# motor6.net
KiCad netlist of a schematic drawn in EAGLE
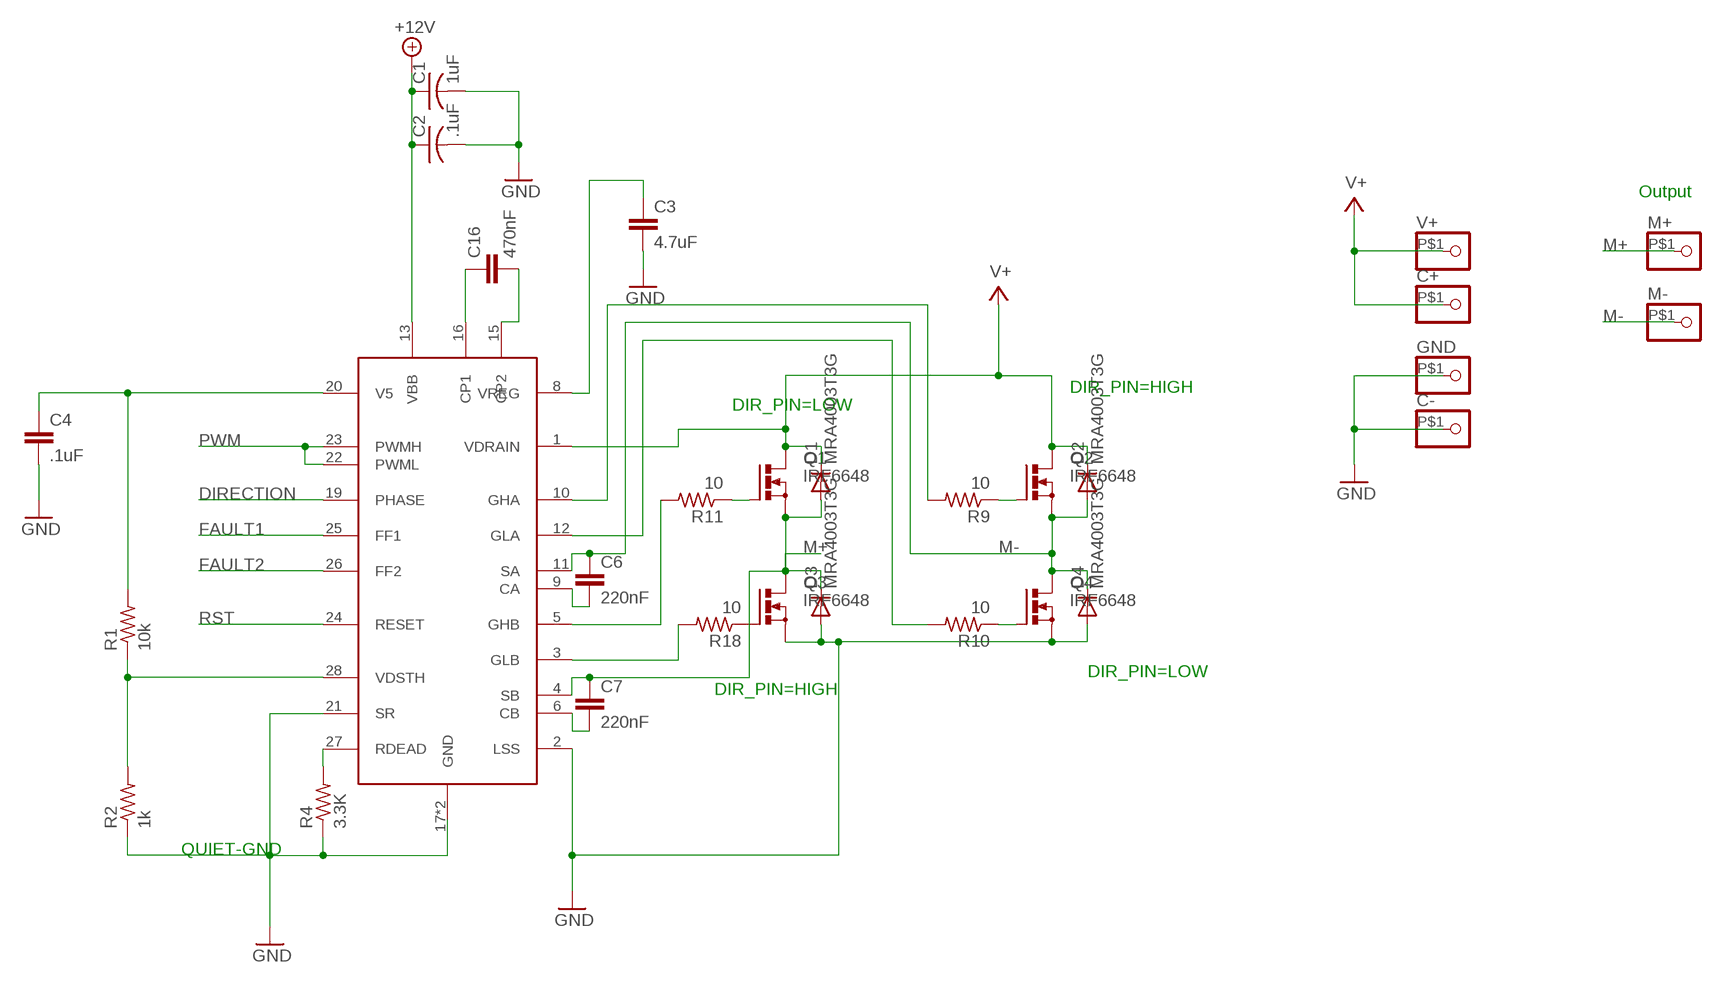
[diagram p0: schematic, sheet 1]
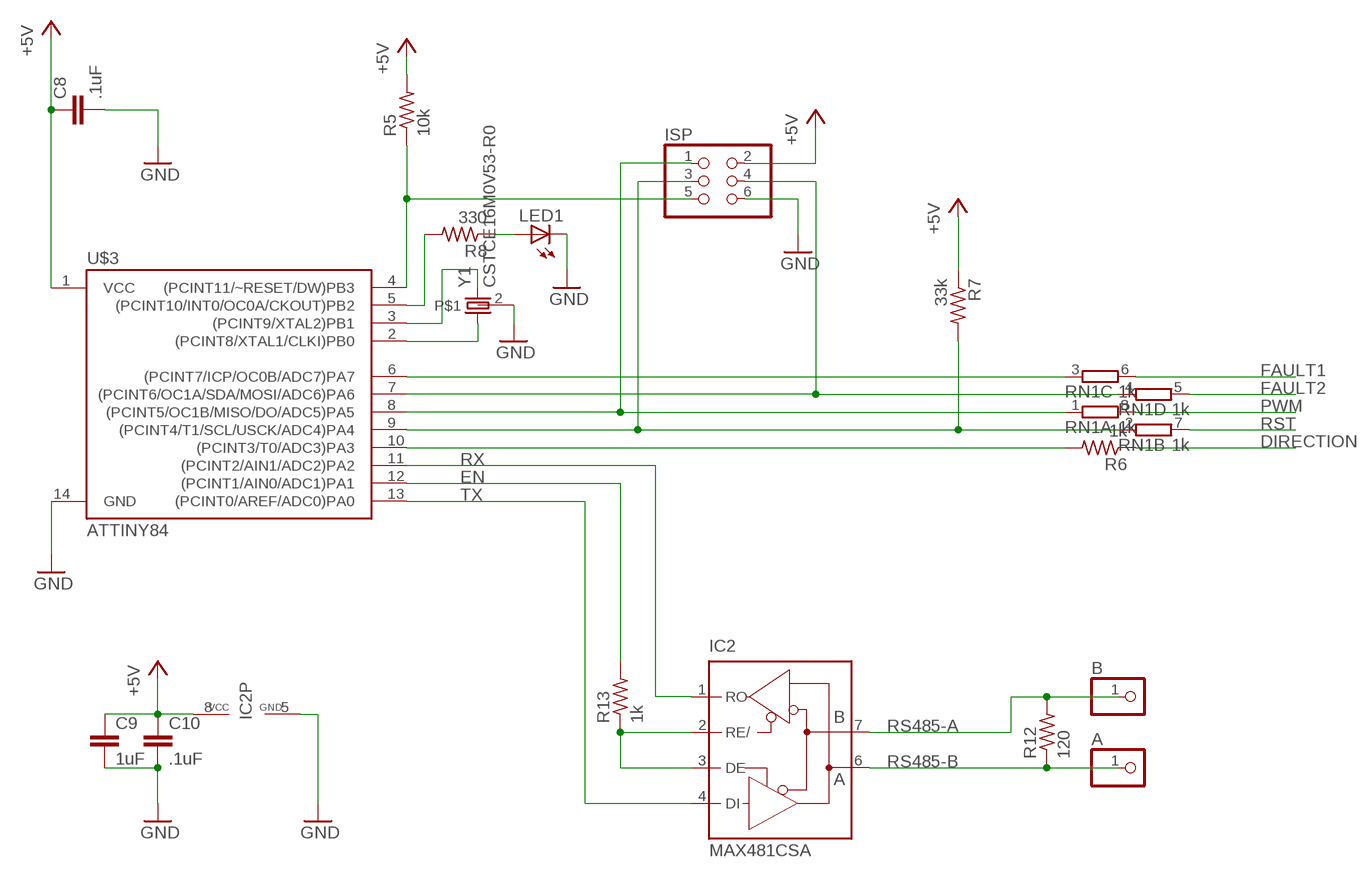
[diagram p1: schematic, sheet 2]
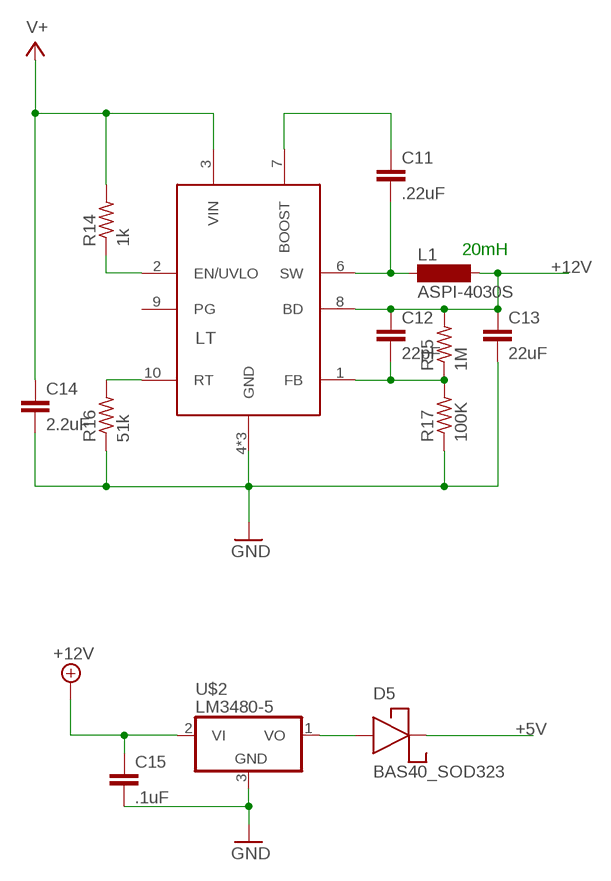
[diagram p2: schematic, sheet 3]

(export (version "E")
  (design (tool "Eeschema 10.0.6"))
  (components
    (comp (ref "C11")
      (value ".22uF")
      (footprint "eagle-import:C0603")
      (libsource (lib "eagle-import") (part "C-EUC0603"))
    )
    (comp (ref "C12")
      (value "22pF")
      (footprint "eagle-import:C0603")
      (libsource (lib "eagle-import") (part "C-EUC0603"))
    )
    (comp (ref "C13")
      (value "22uF")
      (footprint "eagle-import:C0805")
      (libsource (lib "eagle-import") (part "C-EUC0805"))
    )
    (comp (ref "C14")
      (value "2.2uF")
      (footprint "eagle-import:C0603")
      (libsource (lib "eagle-import") (part "C-EUC0603"))
    )
    (comp (ref "C15")
      (value ".1uF")
      (footprint "eagle-import:C0603")
      (libsource (lib "eagle-import") (part "C-EUC0603"))
    )
    (comp (ref "D5")
      (value "BAS40_SOD323")
      (footprint "eagle-import:SOD323")
      (libsource (lib "eagle-import") (part "BAS40_SOD323"))
    )
    (comp (ref "L1")
      (value "ASPI-4030S")
      (footprint "eagle-import:ASPI-4030S")
      (libsource (lib "eagle-import") (part "ASPI-4030S"))
    )
    (comp (ref "LT")
      (value "LT3990")
      (footprint "eagle-import:DFN10-3X3")
      (libsource (lib "eagle-import") (part "LT3990"))
    )
    (comp (ref "R14")
      (value "1k")
      (footprint "eagle-import:R0603")
      (libsource (lib "eagle-import") (part "R-US_R0603"))
    )
    (comp (ref "R15")
      (value "1M")
      (footprint "eagle-import:R0603")
      (libsource (lib "eagle-import") (part "R-US_R0603"))
    )
    (comp (ref "R16")
      (value "51k")
      (footprint "eagle-import:R0603")
      (libsource (lib "eagle-import") (part "R-US_R0603"))
    )
    (comp (ref "R17")
      (value "100K")
      (footprint "eagle-import:R0603")
      (libsource (lib "eagle-import") (part "R-US_R0603"))
    )
    (comp (ref "U$2")
      (value "LM3480-5")
      (footprint "eagle-import:SOT23")
      (libsource (lib "eagle-import") (part "LM3480-5"))
    )
    (comp (ref "ALLGR")
      (value "ALLEGRO-A3921")
      (footprint "eagle-import:TSSOP28")
      (libsource (lib "eagle-import") (part "ALLEGRO-A3921"))
    )
    (comp (ref "C+")
      (value "PINHD-1X1")
      (footprint "eagle-import:1X01")
      (libsource (lib "eagle-import") (part "PINHD-1X1"))
    )
    (comp (ref "C-")
      (value "PINHD-1X1")
      (footprint "eagle-import:1X01")
      (libsource (lib "eagle-import") (part "PINHD-1X1"))
    )
    (comp (ref "C1")
      (value "1uF")
      (footprint "eagle-import:C0603")
      (libsource (lib "eagle-import") (part "C-USC0603"))
    )
    (comp (ref "C2")
      (value ".1uF")
      (footprint "eagle-import:C0603")
      (libsource (lib "eagle-import") (part "C-USC0603"))
    )
    (comp (ref "C3")
      (value "4.7uF")
      (footprint "eagle-import:C0603")
      (libsource (lib "eagle-import") (part "C-EUC0603"))
    )
    (comp (ref "C4")
      (value ".1uF")
      (footprint "eagle-import:C0603")
      (libsource (lib "eagle-import") (part "C-EUC0603"))
    )
    (comp (ref "C6")
      (value "220nF")
      (footprint "eagle-import:C0603")
      (libsource (lib "eagle-import") (part "C-EUC0603"))
    )
    (comp (ref "C7")
      (value "220nF")
      (footprint "eagle-import:C0603")
      (libsource (lib "eagle-import") (part "C-EUC0603"))
    )
    (comp (ref "C16")
      (value "470nF")
      (footprint "eagle-import:C0603")
      (libsource (lib "eagle-import") (part "C-EUC0603"))
    )
    (comp (ref "D1")
      (value "MRA4003T3G")
      (footprint "eagle-import:SMA")
      (libsource (lib "eagle-import") (part "MRA4003T3G"))
    )
    (comp (ref "D2")
      (value "MRA4003T3G")
      (footprint "eagle-import:SMA")
      (libsource (lib "eagle-import") (part "MRA4003T3G"))
    )
    (comp (ref "D3")
      (value "MRA4003T3G")
      (footprint "eagle-import:SMA")
      (libsource (lib "eagle-import") (part "MRA4003T3G"))
    )
    (comp (ref "D4")
      (value "MRA4003T3G")
      (footprint "eagle-import:SMA")
      (libsource (lib "eagle-import") (part "MRA4003T3G"))
    )
    (comp (ref "GND")
      (value "PINHD-1X1")
      (footprint "eagle-import:1X01")
      (libsource (lib "eagle-import") (part "PINHD-1X1"))
    )
    (comp (ref "M+")
      (value "PINHD-1X1")
      (footprint "eagle-import:1X01")
      (libsource (lib "eagle-import") (part "PINHD-1X1"))
    )
    (comp (ref "M-")
      (value "PINHD-1X1")
      (footprint "eagle-import:1X01")
      (libsource (lib "eagle-import") (part "PINHD-1X1"))
    )
    (comp (ref "Q1")
      (value "IRF6648")
      (footprint "eagle-import:DIRECTFET-MOD")
      (libsource (lib "eagle-import") (part "IRF6648"))
    )
    (comp (ref "Q2")
      (value "IRF6648")
      (footprint "eagle-import:DIRECTFET-MOD")
      (libsource (lib "eagle-import") (part "IRF6648"))
    )
    (comp (ref "Q3")
      (value "IRF6648")
      (footprint "eagle-import:DIRECTFET")
      (libsource (lib "eagle-import") (part "transistor-power_IRF6648"))
    )
    (comp (ref "Q4")
      (value "IRF6648")
      (footprint "eagle-import:DIRECTFET")
      (libsource (lib "eagle-import") (part "transistor-power_IRF6648"))
    )
    (comp (ref "R1")
      (value "10k")
      (footprint "eagle-import:R0603")
      (libsource (lib "eagle-import") (part "R-US_R0603"))
    )
    (comp (ref "R2")
      (value "1k")
      (footprint "eagle-import:R0603")
      (libsource (lib "eagle-import") (part "R-US_R0603"))
    )
    (comp (ref "R4")
      (value "3.3K")
      (footprint "eagle-import:R0603")
      (libsource (lib "eagle-import") (part "R-US_R0603"))
    )
    (comp (ref "R9")
      (value "10")
      (footprint "eagle-import:R0603")
      (libsource (lib "eagle-import") (part "R-US_R0603"))
    )
    (comp (ref "R10")
      (value "10")
      (footprint "eagle-import:R0603")
      (libsource (lib "eagle-import") (part "R-US_R0603"))
    )
    (comp (ref "R11")
      (value "10")
      (footprint "eagle-import:R0603")
      (libsource (lib "eagle-import") (part "R-US_R0603"))
    )
    (comp (ref "R18")
      (value "10")
      (footprint "eagle-import:R0603")
      (libsource (lib "eagle-import") (part "R-US_R0603"))
    )
    (comp (ref "V+")
      (value "PINHD-1X1")
      (footprint "eagle-import:1X01")
      (libsource (lib "eagle-import") (part "PINHD-1X1"))
    )
    (comp (ref "A")
      (value "PINHD-1X1")
      (footprint "eagle-import:1X01")
      (libsource (lib "eagle-import") (part "pinhead_PINHD-1X1"))
    )
    (comp (ref "B")
      (value "PINHD-1X1")
      (footprint "eagle-import:1X01")
      (libsource (lib "eagle-import") (part "pinhead_PINHD-1X1"))
    )
    (comp (ref "C8")
      (value ".1uF")
      (footprint "eagle-import:C0603")
      (libsource (lib "eagle-import") (part "C-EUC0603"))
    )
    (comp (ref "C9")
      (value "1uF")
      (footprint "eagle-import:C0603")
      (libsource (lib "eagle-import") (part "C-EUC0603"))
    )
    (comp (ref "C10")
      (value ".1uF")
      (footprint "eagle-import:C0603")
      (libsource (lib "eagle-import") (part "C-EUC0603"))
    )
    (comp (ref "IC2")
      (value "MAX481CSA")
      (footprint "eagle-import:SO08")
      (fields (field (name "MF") "MAXIM"))
      (libsource (lib "eagle-import") (part "MAX481CSA"))
    )
    (comp (ref "ISP")
      (value "PINHD-2X3")
      (footprint "eagle-import:2X03")
      (libsource (lib "eagle-import") (part "PINHD-2X3"))
    )
    (comp (ref "LED1")
      (value "LEDCHIPLED_0603")
      (footprint "eagle-import:CHIPLED_0603")
      (libsource (lib "eagle-import") (part "LEDCHIPLED_0603"))
    )
    (comp (ref "R5")
      (value "10k")
      (footprint "eagle-import:R0603")
      (libsource (lib "eagle-import") (part "R-US_R0603"))
    )
    (comp (ref "R6")
      (value "1k")
      (footprint "eagle-import:R0603")
      (libsource (lib "eagle-import") (part "R-US_R0603"))
    )
    (comp (ref "R7")
      (value "33k")
      (footprint "eagle-import:R0603")
      (libsource (lib "eagle-import") (part "R-US_R0603"))
    )
    (comp (ref "R8")
      (value "330")
      (footprint "eagle-import:R0603")
      (libsource (lib "eagle-import") (part "R-US_R0603"))
    )
    (comp (ref "R12")
      (value "120")
      (footprint "eagle-import:R0603")
      (libsource (lib "eagle-import") (part "R-US_R0603"))
    )
    (comp (ref "R13")
      (value "1k")
      (footprint "eagle-import:R0603")
      (libsource (lib "eagle-import") (part "R-US_R0603"))
    )
    (comp (ref "RN1")
      (value "1k")
      (footprint "eagle-import:EXB38V")
      (libsource (lib "eagle-import") (part "4R-NEXB38V"))
    )
    (comp (ref "U$3")
      (value "ATTINY84")
      (footprint "eagle-import:SO14")
      (libsource (lib "eagle-import") (part "ATTINY84"))
    )
    (comp (ref "Y1")
      (value "CSTCE16M0V53-R0")
      (footprint "eagle-import:MYSMD2_RESONATOR")
      (libsource (lib "eagle-import") (part "CSTCE16M0V53-R0"))
    )
  )
  (nets
    (net (code "1") (name "+5V") (class "Default")
      (node (ref "C10") (pin "1") (pinfunction "1_1") (pintype "passive"))
      (node (ref "C8") (pin "1") (pinfunction "1_1") (pintype "passive"))
      (node (ref "C9") (pin "1") (pinfunction "1_1") (pintype "passive"))
      (node (ref "D5") (pin "1") (pinfunction "P$2_1") (pintype "bidirectional"))
      (node (ref "IC2") (pin "8") (pinfunction "VCC_8") (pintype "power_in"))
      (node (ref "ISP") (pin "2") (pinfunction "2_2") (pintype "passive"))
      (node (ref "R5") (pin "2") (pinfunction "2_2") (pintype "passive"))
      (node (ref "R7") (pin "1") (pinfunction "1_1") (pintype "passive"))
      (node (ref "U$3") (pin "1") (pinfunction "VCC_1") (pintype "bidirectional"))
    )
    (net (code "2") (name "+12V") (class "Default")
      (node (ref "ALLGR") (pin "13") (pinfunction "VBB_13") (pintype "bidirectional"))
      (node (ref "C1") (pin "1") (pinfunction "1_1") (pintype "passive"))
      (node (ref "C12") (pin "1") (pinfunction "1_1") (pintype "passive"))
      (node (ref "C13") (pin "1") (pinfunction "1_1") (pintype "passive"))
      (node (ref "C15") (pin "1") (pinfunction "1_1") (pintype "passive"))
      (node (ref "C2") (pin "1") (pinfunction "1_1") (pintype "passive"))
      (node (ref "L1") (pin "P$2") (pinfunction "2_P$2") (pintype "passive"))
      (node (ref "LT") (pin "8") (pinfunction "BD_8") (pintype "bidirectional"))
      (node (ref "R15") (pin "2") (pinfunction "2_2") (pintype "passive"))
      (node (ref "U$2") (pin "2") (pinfunction "VI_2") (pintype "input"))
    )
    (net (code "3") (name "DIRECTION") (class "Default")
      (node (ref "ALLGR") (pin "19") (pinfunction "PHASE_19") (pintype "bidirectional"))
      (node (ref "R6") (pin "1") (pinfunction "1_1") (pintype "passive"))
    )
    (net (code "4") (name "EN") (class "Default")
      (node (ref "R13") (pin "2") (pinfunction "2_2") (pintype "passive"))
      (node (ref "U$3") (pin "12") (pinfunction "(PCINT1/AIN0/ADC1)PA1_12") (pintype "bidirectional"))
    )
    (net (code "5") (name "FAULT1") (class "Default")
      (node (ref "ALLGR") (pin "25") (pinfunction "FF1_25") (pintype "bidirectional"))
      (node (ref "RN1") (pin "6") (pinfunction "2_6") (pintype "passive"))
    )
    (net (code "6") (name "FAULT2") (class "Default")
      (node (ref "ALLGR") (pin "26") (pinfunction "FF2_26") (pintype "bidirectional"))
      (node (ref "RN1") (pin "5") (pinfunction "2_5") (pintype "passive"))
    )
    (net (code "7") (name "GND") (class "Default")
      (node (ref "ALLGR") (pin "17") (pinfunction "GND_17") (pintype "bidirectional"))
      (node (ref "ALLGR") (pin "2") (pinfunction "LSS_2") (pintype "bidirectional"))
      (node (ref "ALLGR") (pin "21") (pinfunction "SR_21") (pintype "bidirectional"))
      (node (ref "ALLGR") (pin "P$1") (pinfunction "GND_P$1") (pintype "bidirectional"))
      (node (ref "C-") (pin "P$1") (pinfunction "1_P$1") (pintype "passive"))
      (node (ref "C1") (pin "2") (pinfunction "2_2") (pintype "passive"))
      (node (ref "C10") (pin "2") (pinfunction "2_2") (pintype "passive"))
      (node (ref "C13") (pin "2") (pinfunction "2_2") (pintype "passive"))
      (node (ref "C14") (pin "2") (pinfunction "2_2") (pintype "passive"))
      (node (ref "C15") (pin "2") (pinfunction "2_2") (pintype "passive"))
      (node (ref "C2") (pin "2") (pinfunction "2_2") (pintype "passive"))
      (node (ref "C3") (pin "2") (pinfunction "2_2") (pintype "passive"))
      (node (ref "C4") (pin "2") (pinfunction "2_2") (pintype "passive"))
      (node (ref "C8") (pin "2") (pinfunction "2_2") (pintype "passive"))
      (node (ref "C9") (pin "2") (pinfunction "2_2") (pintype "passive"))
      (node (ref "D3") (pin "A") (pinfunction "A_A") (pintype "passive"))
      (node (ref "D4") (pin "A") (pinfunction "A_A") (pintype "passive"))
      (node (ref "GND") (pin "P$1") (pinfunction "1_P$1") (pintype "passive"))
      (node (ref "IC2") (pin "5") (pinfunction "GND_5") (pintype "power_in"))
      (node (ref "ISP") (pin "6") (pinfunction "6_6") (pintype "passive"))
      (node (ref "LED1") (pin "C") (pinfunction "C_C") (pintype "passive"))
      (node (ref "LT") (pin "4") (pinfunction "GND_4") (pintype "bidirectional"))
      (node (ref "LT") (pin "5") (pinfunction "GND_5") (pintype "bidirectional"))
      (node (ref "LT") (pin "EXP") (pinfunction "GND_EXP") (pintype "bidirectional"))
      (node (ref "Q3") (pin "S@1") (pinfunction "S_S@1") (pintype "passive"))
      (node (ref "Q3") (pin "S@2") (pinfunction "S_S@2") (pintype "passive"))
      (node (ref "Q4") (pin "S@1") (pinfunction "S_S@1") (pintype "passive"))
      (node (ref "Q4") (pin "S@2") (pinfunction "S_S@2") (pintype "passive"))
      (node (ref "R16") (pin "1") (pinfunction "1_1") (pintype "passive"))
      (node (ref "R17") (pin "1") (pinfunction "1_1") (pintype "passive"))
      (node (ref "R2") (pin "1") (pinfunction "1_1") (pintype "passive"))
      (node (ref "R4") (pin "1") (pinfunction "1_1") (pintype "passive"))
      (node (ref "U$2") (pin "3") (pinfunction "GND_3") (pintype "input"))
      (node (ref "U$3") (pin "14") (pinfunction "GND_14") (pintype "bidirectional"))
      (node (ref "Y1") (pin "2") (pinfunction "P$1_2") (pintype "bidirectional"))
    )
    (net (code "8") (name "M+") (class "Default")
      (node (ref "ALLGR") (pin "4") (pinfunction "SB_4") (pintype "bidirectional"))
      (node (ref "C7") (pin "1") (pinfunction "1_1") (pintype "passive"))
      (node (ref "D1") (pin "A") (pinfunction "A_A") (pintype "passive"))
      (node (ref "D3") (pin "C") (pinfunction "C_C") (pintype "passive"))
      (node (ref "M+") (pin "P$1") (pinfunction "1_P$1") (pintype "passive"))
      (node (ref "Q1") (pin "S@1") (pinfunction "S_S@1") (pintype "passive"))
      (node (ref "Q1") (pin "S@2") (pinfunction "S_S@2") (pintype "passive"))
      (node (ref "Q3") (pin "D@1") (pinfunction "D_D@1") (pintype "passive"))
      (node (ref "Q3") (pin "D@2") (pinfunction "D_D@2") (pintype "passive"))
      (node (ref "Q3") (pin "D@3") (pinfunction "D_D@3") (pintype "passive"))
      (node (ref "Q3") (pin "D@4") (pinfunction "D_D@4") (pintype "passive"))
    )
    (net (code "9") (name "M-") (class "Default")
      (node (ref "ALLGR") (pin "11") (pinfunction "SA_11") (pintype "bidirectional"))
      (node (ref "C6") (pin "1") (pinfunction "1_1") (pintype "passive"))
      (node (ref "D2") (pin "A") (pinfunction "A_A") (pintype "passive"))
      (node (ref "D4") (pin "C") (pinfunction "C_C") (pintype "passive"))
      (node (ref "M-") (pin "P$1") (pinfunction "1_P$1") (pintype "passive"))
      (node (ref "Q2") (pin "S@1") (pinfunction "S_S@1") (pintype "passive"))
      (node (ref "Q2") (pin "S@2") (pinfunction "S_S@2") (pintype "passive"))
      (node (ref "Q4") (pin "D@1") (pinfunction "D_D@1") (pintype "passive"))
      (node (ref "Q4") (pin "D@2") (pinfunction "D_D@2") (pintype "passive"))
      (node (ref "Q4") (pin "D@3") (pinfunction "D_D@3") (pintype "passive"))
      (node (ref "Q4") (pin "D@4") (pinfunction "D_D@4") (pintype "passive"))
    )
    (net (code "10") (name "Net-(ALLGR-CA)") (class "Default")
      (node (ref "ALLGR") (pin "9") (pinfunction "CA_9") (pintype "bidirectional"))
      (node (ref "C6") (pin "2") (pinfunction "2_2") (pintype "passive"))
    )
    (net (code "11") (name "Net-(ALLGR-CB)") (class "Default")
      (node (ref "ALLGR") (pin "6") (pinfunction "CB_6") (pintype "bidirectional"))
      (node (ref "C7") (pin "2") (pinfunction "2_2") (pintype "passive"))
    )
    (net (code "12") (name "Net-(ALLGR-CP1)") (class "Default")
      (node (ref "ALLGR") (pin "16") (pinfunction "CP1_16") (pintype "bidirectional"))
      (node (ref "C16") (pin "1") (pinfunction "1_1") (pintype "passive"))
    )
    (net (code "13") (name "Net-(ALLGR-CP2)") (class "Default")
      (node (ref "ALLGR") (pin "15") (pinfunction "CP2_15") (pintype "bidirectional"))
      (node (ref "C16") (pin "2") (pinfunction "2_2") (pintype "passive"))
    )
    (net (code "14") (name "Net-(ALLGR-GHA)") (class "Default")
      (node (ref "ALLGR") (pin "10") (pinfunction "GHA_10") (pintype "bidirectional"))
      (node (ref "R9") (pin "2") (pinfunction "2_2") (pintype "passive"))
    )
    (net (code "15") (name "Net-(ALLGR-GHB)") (class "Default")
      (node (ref "ALLGR") (pin "5") (pinfunction "GHB_5") (pintype "bidirectional"))
      (node (ref "R11") (pin "2") (pinfunction "2_2") (pintype "passive"))
    )
    (net (code "16") (name "Net-(ALLGR-GLA)") (class "Default")
      (node (ref "ALLGR") (pin "12") (pinfunction "GLA_12") (pintype "bidirectional"))
      (node (ref "R10") (pin "2") (pinfunction "2_2") (pintype "passive"))
    )
    (net (code "17") (name "Net-(ALLGR-GLB)") (class "Default")
      (node (ref "ALLGR") (pin "3") (pinfunction "GLB_3") (pintype "bidirectional"))
      (node (ref "R18") (pin "2") (pinfunction "2_2") (pintype "passive"))
    )
    (net (code "18") (name "Net-(ALLGR-RDEAD)") (class "Default")
      (node (ref "ALLGR") (pin "27") (pinfunction "RDEAD_27") (pintype "bidirectional"))
      (node (ref "R4") (pin "2") (pinfunction "2_2") (pintype "passive"))
    )
    (net (code "19") (name "Net-(ALLGR-V5)") (class "Default")
      (node (ref "ALLGR") (pin "20") (pinfunction "V5_20") (pintype "bidirectional"))
      (node (ref "C4") (pin "1") (pinfunction "1_1") (pintype "passive"))
      (node (ref "R1") (pin "2") (pinfunction "2_2") (pintype "passive"))
    )
    (net (code "20") (name "Net-(ALLGR-VDSTH)") (class "Default")
      (node (ref "ALLGR") (pin "28") (pinfunction "VDSTH_28") (pintype "bidirectional"))
      (node (ref "R1") (pin "1") (pinfunction "1_1") (pintype "passive"))
      (node (ref "R2") (pin "2") (pinfunction "2_2") (pintype "passive"))
    )
    (net (code "21") (name "Net-(ALLGR-VREG)") (class "Default")
      (node (ref "ALLGR") (pin "8") (pinfunction "VREG_8") (pintype "bidirectional"))
      (node (ref "C3") (pin "1") (pinfunction "1_1") (pintype "passive"))
    )
    (net (code "22") (name "Net-(D5-P$1)") (class "Default")
      (node (ref "D5") (pin "2") (pinfunction "P$1_2") (pintype "bidirectional"))
      (node (ref "U$2") (pin "1") (pinfunction "VO_1") (pintype "passive"))
    )
    (net (code "23") (name "Net-(IC2A-DE)") (class "Default")
      (node (ref "IC2") (pin "2") (pinfunction "RE/_2") (pintype "input"))
      (node (ref "IC2") (pin "3") (pinfunction "DE_3") (pintype "input"))
      (node (ref "R13") (pin "1") (pinfunction "1_1") (pintype "passive"))
    )
    (net (code "24") (name "Net-(L1-1)") (class "Default")
      (node (ref "C11") (pin "2") (pinfunction "2_2") (pintype "passive"))
      (node (ref "L1") (pin "P$1") (pinfunction "1_P$1") (pintype "passive"))
      (node (ref "LT") (pin "6") (pinfunction "SW_6") (pintype "bidirectional"))
    )
    (net (code "25") (name "Net-(LED1-PadA)") (class "Default")
      (node (ref "LED1") (pin "A") (pinfunction "A_A") (pintype "passive"))
      (node (ref "R8") (pin "1") (pinfunction "1_1") (pintype "passive"))
    )
    (net (code "26") (name "Net-(LT-BOOST)") (class "Default")
      (node (ref "C11") (pin "1") (pinfunction "1_1") (pintype "passive"))
      (node (ref "LT") (pin "7") (pinfunction "BOOST_7") (pintype "bidirectional"))
    )
    (net (code "27") (name "Net-(LT-EN{slash}UVLO)") (class "Default")
      (node (ref "LT") (pin "2") (pinfunction "EN/UVLO_2") (pintype "bidirectional"))
      (node (ref "R14") (pin "1") (pinfunction "1_1") (pintype "passive"))
    )
    (net (code "28") (name "Net-(LT-FB)") (class "Default")
      (node (ref "C12") (pin "2") (pinfunction "2_2") (pintype "passive"))
      (node (ref "LT") (pin "1") (pinfunction "FB_1") (pintype "bidirectional"))
      (node (ref "R15") (pin "1") (pinfunction "1_1") (pintype "passive"))
      (node (ref "R17") (pin "2") (pinfunction "2_2") (pintype "passive"))
    )
    (net (code "29") (name "Net-(LT-RT)") (class "Default")
      (node (ref "LT") (pin "10") (pinfunction "RT_10") (pintype "bidirectional"))
      (node (ref "R16") (pin "2") (pinfunction "2_2") (pintype "passive"))
    )
    (net (code "30") (name "Net-(Q1-PadG)") (class "Default")
      (node (ref "Q1") (pin "G") (pinfunction "G_G") (pintype "passive"))
      (node (ref "R11") (pin "1") (pinfunction "1_1") (pintype "passive"))
    )
    (net (code "31") (name "Net-(Q2-PadG)") (class "Default")
      (node (ref "Q2") (pin "G") (pinfunction "G_G") (pintype "passive"))
      (node (ref "R9") (pin "1") (pinfunction "1_1") (pintype "passive"))
    )
    (net (code "32") (name "Net-(Q3-PadG)") (class "Default")
      (node (ref "Q3") (pin "G") (pinfunction "G_G") (pintype "passive"))
      (node (ref "R18") (pin "1") (pinfunction "1_1") (pintype "passive"))
    )
    (net (code "33") (name "Net-(Q4-PadG)") (class "Default")
      (node (ref "Q4") (pin "G") (pinfunction "G_G") (pintype "passive"))
      (node (ref "R10") (pin "1") (pinfunction "1_1") (pintype "passive"))
    )
    (net (code "34") (name "Net-(RN1B-1)") (class "Default")
      (node (ref "ISP") (pin "3") (pinfunction "3_3") (pintype "passive"))
      (node (ref "R7") (pin "2") (pinfunction "2_2") (pintype "passive"))
      (node (ref "RN1") (pin "2") (pinfunction "1_2") (pintype "passive"))
      (node (ref "U$3") (pin "9") (pinfunction "(PCINT4/T1/SCL/USCK/ADC4)PA4_9") (pintype "bidirectional"))
    )
    (net (code "35") (name "Net-(RN1C-1)") (class "Default")
      (node (ref "RN1") (pin "3") (pinfunction "1_3") (pintype "passive"))
      (node (ref "U$3") (pin "6") (pinfunction "(PCINT7/ICP/OC0B/ADC7)PA7_6") (pintype "bidirectional"))
    )
    (net (code "36") (name "Net-(RN1D-1)") (class "Default")
      (node (ref "ISP") (pin "4") (pinfunction "4_4") (pintype "passive"))
      (node (ref "RN1") (pin "4") (pinfunction "1_4") (pintype "passive"))
      (node (ref "U$3") (pin "7") (pinfunction "(PCINT6/OC1A/SDA/MOSI/ADC6)PA6_7") (pintype "bidirectional"))
    )
    (net (code "37") (name "Net-(U$3-(PCINT3{slash}T0{slash}ADC3)PA3)") (class "Default")
      (node (ref "R6") (pin "2") (pinfunction "2_2") (pintype "passive"))
      (node (ref "U$3") (pin "10") (pinfunction "(PCINT3/T0/ADC3)PA3_10") (pintype "bidirectional"))
    )
    (net (code "38") (name "Net-(U$3-(PCINT5{slash}OC1B{slash}MISO{slash}DO{slash}ADC5)PA5)") (class "Default")
      (node (ref "ISP") (pin "1") (pinfunction "1_1") (pintype "passive"))
      (node (ref "RN1") (pin "1") (pinfunction "1_1") (pintype "passive"))
      (node (ref "U$3") (pin "8") (pinfunction "(PCINT5/OC1B/MISO/DO/ADC5)PA5_8") (pintype "bidirectional"))
    )
    (net (code "39") (name "Net-(U$3-(PCINT8{slash}XTAL1{slash}CLKI)PB0)") (class "Default")
      (node (ref "U$3") (pin "2") (pinfunction "(PCINT8/XTAL1/CLKI)PB0_2") (pintype "bidirectional"))
      (node (ref "Y1") (pin "1") (pinfunction "1_1") (pintype "passive"))
    )
    (net (code "40") (name "Net-(U$3-(PCINT9{slash}XTAL2)PB1)") (class "Default")
      (node (ref "U$3") (pin "3") (pinfunction "(PCINT9/XTAL2)PB1_3") (pintype "bidirectional"))
      (node (ref "Y1") (pin "3") (pinfunction "2_3") (pintype "passive"))
    )
    (net (code "41") (name "Net-(U$3-(PCINT10{slash}INT0{slash}OC0A{slash}CKOUT)PB2)") (class "Default")
      (node (ref "R8") (pin "2") (pinfunction "2_2") (pintype "passive"))
      (node (ref "U$3") (pin "5") (pinfunction "(PCINT10/INT0/OC0A/CKOUT)PB2_5") (pintype "bidirectional"))
    )
    (net (code "42") (name "Net-(U$3-(PCINT11{slash}~{RESET{slash}DW})PB3)") (class "Default")
      (node (ref "ISP") (pin "5") (pinfunction "5_5") (pintype "passive"))
      (node (ref "R5") (pin "1") (pinfunction "1_1") (pintype "passive"))
      (node (ref "U$3") (pin "4") (pinfunction "(PCINT11/~{RESET/DW})PB3_4") (pintype "bidirectional"))
    )
    (net (code "43") (name "PWM") (class "Default")
      (node (ref "ALLGR") (pin "22") (pinfunction "PWML_22") (pintype "bidirectional"))
      (node (ref "ALLGR") (pin "23") (pinfunction "PWMH_23") (pintype "bidirectional"))
      (node (ref "RN1") (pin "8") (pinfunction "2_8") (pintype "passive"))
    )
    (net (code "44") (name "RS485-A") (class "Default")
      (node (ref "B") (pin "1") (pinfunction "1_1") (pintype "passive"))
      (node (ref "IC2") (pin "7") (pinfunction "B_7") (pintype "passive"))
      (node (ref "R12") (pin "2") (pinfunction "2_2") (pintype "passive"))
    )
    (net (code "45") (name "RS485-B") (class "Default")
      (node (ref "A") (pin "1") (pinfunction "1_1") (pintype "passive"))
      (node (ref "IC2") (pin "6") (pinfunction "A_6") (pintype "passive"))
      (node (ref "R12") (pin "1") (pinfunction "1_1") (pintype "passive"))
    )
    (net (code "46") (name "RST") (class "Default")
      (node (ref "ALLGR") (pin "24") (pinfunction "RESET_24") (pintype "bidirectional"))
      (node (ref "RN1") (pin "7") (pinfunction "2_7") (pintype "passive"))
    )
    (net (code "47") (name "RX") (class "Default")
      (node (ref "IC2") (pin "1") (pinfunction "RO_1") (pintype "output"))
      (node (ref "U$3") (pin "11") (pinfunction "(PCINT2/AIN1/ADC2)PA2_11") (pintype "bidirectional"))
    )
    (net (code "48") (name "TX") (class "Default")
      (node (ref "IC2") (pin "4") (pinfunction "DI_4") (pintype "input"))
      (node (ref "U$3") (pin "13") (pinfunction "(PCINT0/AREF/ADC0)PA0_13") (pintype "bidirectional"))
    )
    (net (code "49") (name "V+") (class "Default")
      (node (ref "ALLGR") (pin "1") (pinfunction "VDRAIN_1") (pintype "bidirectional"))
      (node (ref "C+") (pin "P$1") (pinfunction "1_P$1") (pintype "passive"))
      (node (ref "C14") (pin "1") (pinfunction "1_1") (pintype "passive"))
      (node (ref "D1") (pin "C") (pinfunction "C_C") (pintype "passive"))
      (node (ref "D2") (pin "C") (pinfunction "C_C") (pintype "passive"))
      (node (ref "LT") (pin "3") (pinfunction "VIN_3") (pintype "bidirectional"))
      (node (ref "Q1") (pin "D@1") (pinfunction "D_D@1") (pintype "passive"))
      (node (ref "Q1") (pin "D@2") (pinfunction "D_D@2") (pintype "passive"))
      (node (ref "Q1") (pin "D@3") (pinfunction "D_D@3") (pintype "passive"))
      (node (ref "Q1") (pin "D@4") (pinfunction "D_D@4") (pintype "passive"))
      (node (ref "Q2") (pin "D@1") (pinfunction "D_D@1") (pintype "passive"))
      (node (ref "Q2") (pin "D@2") (pinfunction "D_D@2") (pintype "passive"))
      (node (ref "Q2") (pin "D@3") (pinfunction "D_D@3") (pintype "passive"))
      (node (ref "Q2") (pin "D@4") (pinfunction "D_D@4") (pintype "passive"))
      (node (ref "R14") (pin "2") (pinfunction "2_2") (pintype "passive"))
      (node (ref "V+") (pin "P$1") (pinfunction "1_P$1") (pintype "passive"))
    )
    (net (code "50") (name "unconnected-(LT-PG-Pad9)") (class "Default")
      (node (ref "LT") (pin "9") (pinfunction "PG_9") (pintype "bidirectional"))
    )
  )
)
